# esplash.net
KiCad netlist of a schematic drawn in EAGLE
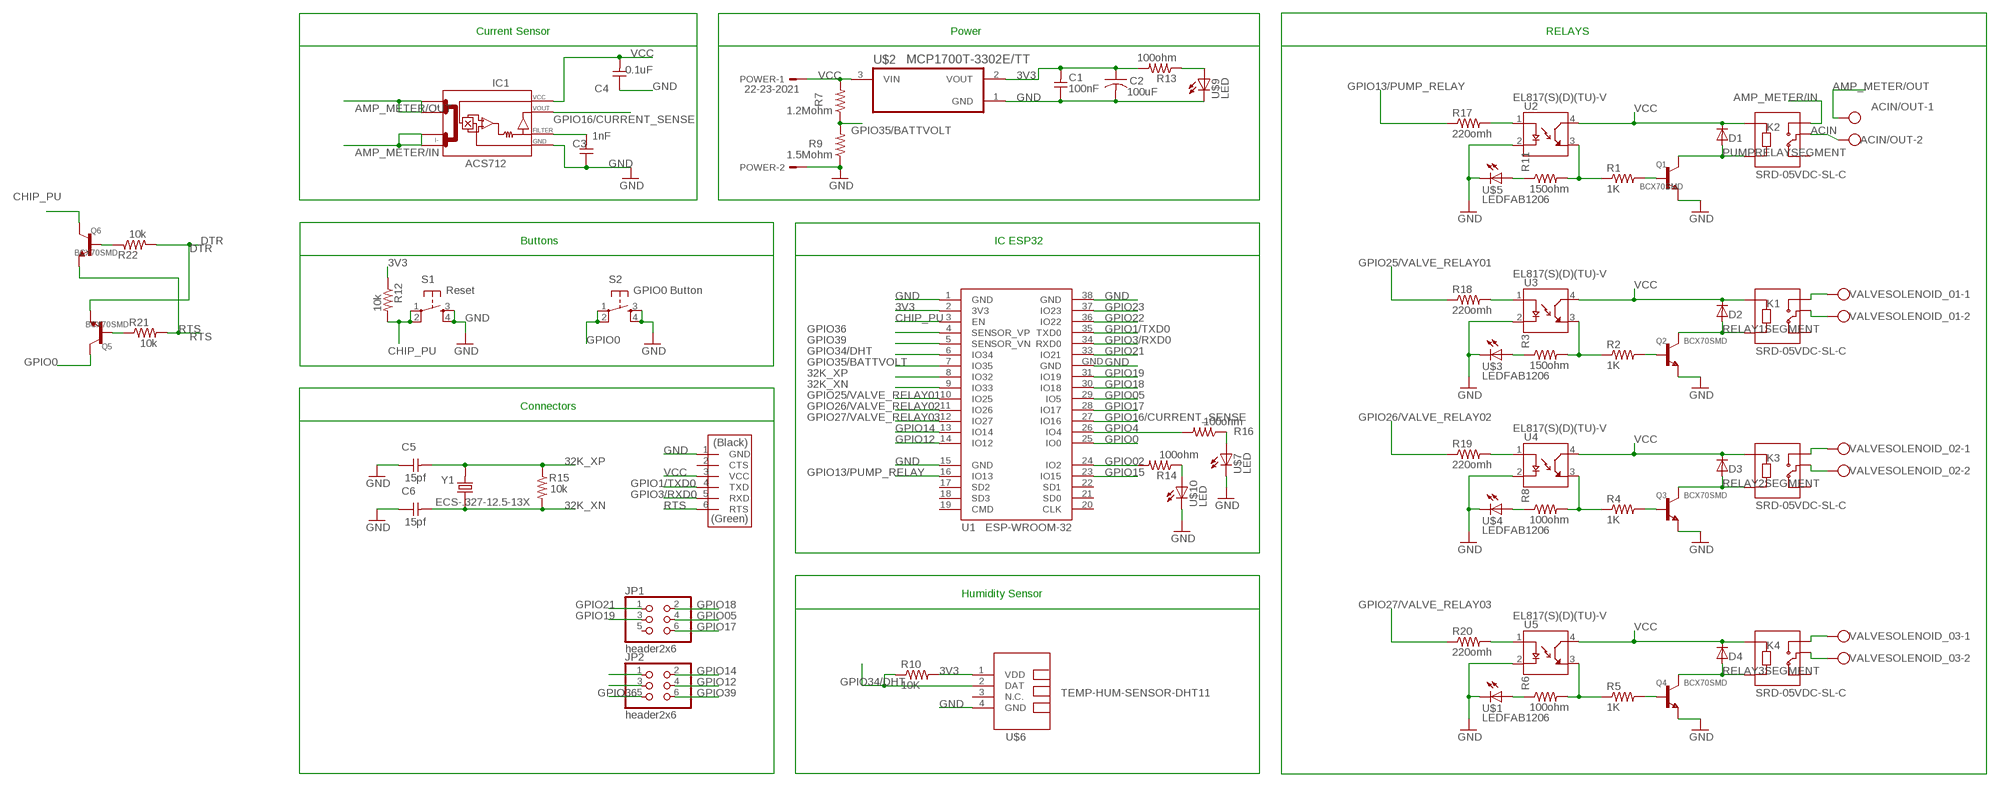
[diagram p0: schematic, sheet 1]

(export (version "E")
  (design (tool "Eeschema 10.0.6"))
  (components
    (comp (ref "ACIN/OUT")
      (value "W237-102")
      (footprint "eagle-import:W237-102")
      (fields (field (name "MPN") "237-102"))
      (libsource (lib "eagle-import") (part "W237-102"))
    )
    (comp (ref "C1")
      (value "100nF")
      (footprint "eagle-import:C1206FAB")
      (libsource (lib "eagle-import") (part "CAP-UNPOLARIZEDFAB"))
    )
    (comp (ref "C2")
      (value "100uF")
      (footprint "eagle-import:C1206FAB")
      (libsource (lib "eagle-import") (part "CAP-US1206FAB"))
    )
    (comp (ref "C3")
      (value "1nF")
      (footprint "eagle-import:C1206FAB")
      (libsource (lib "eagle-import") (part "CAP-UNPOLARIZEDFAB"))
    )
    (comp (ref "C4")
      (value "0.1uF")
      (footprint "eagle-import:C1206FAB")
      (libsource (lib "eagle-import") (part "CAP-UNPOLARIZEDFAB"))
    )
    (comp (ref "C5")
      (value "15pf")
      (footprint "eagle-import:C1206FAB")
      (libsource (lib "eagle-import") (part "CAP-UNPOLARIZEDFAB"))
    )
    (comp (ref "C6")
      (value "15pf")
      (footprint "eagle-import:C1206FAB")
      (libsource (lib "eagle-import") (part "CAP-UNPOLARIZEDFAB"))
    )
    (comp (ref "D1")
      (value "DIODESOD123")
      (footprint "eagle-import:SOD123")
      (libsource (lib "eagle-import") (part "DIODESOD123"))
    )
    (comp (ref "D2")
      (value "DIODESOD123")
      (footprint "eagle-import:SOD123")
      (libsource (lib "eagle-import") (part "DIODESOD123"))
    )
    (comp (ref "D3")
      (value "DIODESOD123")
      (footprint "eagle-import:SOD123")
      (libsource (lib "eagle-import") (part "DIODESOD123"))
    )
    (comp (ref "D4")
      (value "DIODESOD123")
      (footprint "eagle-import:SOD123")
      (libsource (lib "eagle-import") (part "DIODESOD123"))
    )
    (comp (ref "IC1")
      (value "ACS712")
      (footprint "eagle-import:SO08")
      (libsource (lib "eagle-import") (part "ACS712"))
    )
    (comp (ref "JP1")
      (value "header2x6")
      (footprint "eagle-import:2X03")
      (libsource (lib "eagle-import") (part "PINHD-2X3"))
    )
    (comp (ref "JP2")
      (value "header2x6")
      (footprint "eagle-import:2X03")
      (libsource (lib "eagle-import") (part "PINHD-2X3"))
    )
    (comp (ref "K1")
      (value "SRD-05VDC-SL-C")
      (footprint "eagle-import:RELAY_SRD-05VDC-SL-C")
      (fields (field (name "MF") "Songle Relay"))
      (libsource (lib "eagle-import") (part "SRD-05VDC-SL-C"))
    )
    (comp (ref "K2")
      (value "SRD-05VDC-SL-C")
      (footprint "eagle-import:RELAY_SRD-05VDC-SL-C")
      (fields (field (name "MF") "Songle Relay"))
      (libsource (lib "eagle-import") (part "SRD-05VDC-SL-C"))
    )
    (comp (ref "K3")
      (value "SRD-05VDC-SL-C")
      (footprint "eagle-import:RELAY_SRD-05VDC-SL-C")
      (fields (field (name "MF") "Songle Relay"))
      (libsource (lib "eagle-import") (part "SRD-05VDC-SL-C"))
    )
    (comp (ref "K4")
      (value "SRD-05VDC-SL-C")
      (footprint "eagle-import:RELAY_SRD-05VDC-SL-C")
      (fields (field (name "MF") "Songle Relay"))
      (libsource (lib "eagle-import") (part "SRD-05VDC-SL-C"))
    )
    (comp (ref "POWER")
      (value "22-23-2021")
      (footprint "eagle-import:22-23-2021")
      (fields (field (name "MF") "MOLEX"))
      (libsource (lib "eagle-import") (part "22-23-2021"))
    )
    (comp (ref "Q1")
      (value "BCX70SMD")
      (footprint "eagle-import:SOT23")
      (libsource (lib "eagle-import") (part "BCX70SMD"))
    )
    (comp (ref "Q2")
      (value "BCX70SMD")
      (footprint "eagle-import:SOT23")
      (libsource (lib "eagle-import") (part "BCX70SMD"))
    )
    (comp (ref "Q3")
      (value "BCX70SMD")
      (footprint "eagle-import:SOT23")
      (libsource (lib "eagle-import") (part "BCX70SMD"))
    )
    (comp (ref "Q4")
      (value "BCX70SMD")
      (footprint "eagle-import:SOT23")
      (libsource (lib "eagle-import") (part "BCX70SMD"))
    )
    (comp (ref "Q5")
      (value "BCX70SMD")
      (footprint "eagle-import:SOT23")
      (libsource (lib "eagle-import") (part "BCX70SMD"))
    )
    (comp (ref "Q6")
      (value "BCX70SMD")
      (footprint "eagle-import:SOT23")
      (libsource (lib "eagle-import") (part "BCX70SMD"))
    )
    (comp (ref "R1")
      (value "1K")
      (footprint "eagle-import:R1206FAB")
      (libsource (lib "eagle-import") (part "RES-US1206FAB"))
    )
    (comp (ref "R2")
      (value "1K")
      (footprint "eagle-import:R1206FAB")
      (libsource (lib "eagle-import") (part "RES-US1206FAB"))
    )
    (comp (ref "R3")
      (value "150ohm")
      (footprint "eagle-import:R1206FAB")
      (libsource (lib "eagle-import") (part "RES-US1206FAB"))
    )
    (comp (ref "R4")
      (value "1K")
      (footprint "eagle-import:R1206FAB")
      (libsource (lib "eagle-import") (part "RES-US1206FAB"))
    )
    (comp (ref "R5")
      (value "1K")
      (footprint "eagle-import:R1206FAB")
      (libsource (lib "eagle-import") (part "RES-US1206FAB"))
    )
    (comp (ref "R6")
      (value "100ohm")
      (footprint "eagle-import:R1206FAB")
      (libsource (lib "eagle-import") (part "RES-US1206FAB"))
    )
    (comp (ref "R7")
      (value "1.2Mohm")
      (footprint "eagle-import:R1206FAB")
      (libsource (lib "eagle-import") (part "RES-US1206FAB"))
    )
    (comp (ref "R8")
      (value "100ohm")
      (footprint "eagle-import:R1206FAB")
      (libsource (lib "eagle-import") (part "RES-US1206FAB"))
    )
    (comp (ref "R9")
      (value "1.5Mohm")
      (footprint "eagle-import:R1206FAB")
      (libsource (lib "eagle-import") (part "RES-US1206FAB"))
    )
    (comp (ref "R10")
      (value "10K")
      (footprint "eagle-import:R1206FAB")
      (libsource (lib "eagle-import") (part "RES-US1206FAB"))
    )
    (comp (ref "R11")
      (value "150ohm")
      (footprint "eagle-import:R1206FAB")
      (libsource (lib "eagle-import") (part "RES-US1206FAB"))
    )
    (comp (ref "R12")
      (value "10k")
      (footprint "eagle-import:R1206")
      (libsource (lib "eagle-import") (part "RES-US1206"))
    )
    (comp (ref "R13")
      (value "100ohm")
      (footprint "eagle-import:R1206")
      (libsource (lib "eagle-import") (part "RES-US1206"))
    )
    (comp (ref "R14")
      (value "100ohm")
      (footprint "eagle-import:R1206")
      (libsource (lib "eagle-import") (part "RES-US1206"))
    )
    (comp (ref "R15")
      (value "10k")
      (footprint "eagle-import:R1206")
      (libsource (lib "eagle-import") (part "RES-US1206"))
    )
    (comp (ref "R16")
      (value "100ohm")
      (footprint "eagle-import:R1206")
      (libsource (lib "eagle-import") (part "RES-US1206"))
    )
    (comp (ref "R17")
      (value "220omh")
      (footprint "eagle-import:R1206FAB")
      (libsource (lib "eagle-import") (part "RES-US1206FAB"))
    )
    (comp (ref "R18")
      (value "220omh")
      (footprint "eagle-import:R1206FAB")
      (libsource (lib "eagle-import") (part "RES-US1206FAB"))
    )
    (comp (ref "R19")
      (value "220omh")
      (footprint "eagle-import:R1206FAB")
      (libsource (lib "eagle-import") (part "RES-US1206FAB"))
    )
    (comp (ref "R20")
      (value "220omh")
      (footprint "eagle-import:R1206FAB")
      (libsource (lib "eagle-import") (part "RES-US1206FAB"))
    )
    (comp (ref "R21")
      (value "10k")
      (footprint "eagle-import:R1206")
      (libsource (lib "eagle-import") (part "RES-US1206"))
    )
    (comp (ref "R22")
      (value "10k")
      (footprint "eagle-import:R1206")
      (libsource (lib "eagle-import") (part "RES-US1206"))
    )
    (comp (ref "RTS")
      (value "FTDI-SMD-HEADER")
      (footprint "eagle-import:1X06SMD")
      (libsource (lib "eagle-import") (part "FTDI-SMD-HEADER"))
    )
    (comp (ref "S1")
      (value "Reset")
      (footprint "eagle-import:6MM_SWITCH")
      (libsource (lib "eagle-import") (part "6MM_SWITCH6MM_SWITCH"))
    )
    (comp (ref "S2")
      (value "GPIO0 Button")
      (footprint "eagle-import:6MM_SWITCH")
      (libsource (lib "eagle-import") (part "6MM_SWITCH6MM_SWITCH"))
    )
    (comp (ref "U$1")
      (value "LEDFAB1206")
      (footprint "eagle-import:LED1206FAB")
      (libsource (lib "eagle-import") (part "LEDFAB1206"))
    )
    (comp (ref "U$2")
      (value "MCP1700T-3302E/TT")
      (footprint "eagle-import:SOT95P237X112-3N")
      (fields (field (name "MF") "Microchip Technology"))
      (libsource (lib "eagle-import") (part "MCP1700T-3302E/TT"))
    )
    (comp (ref "U$3")
      (value "LEDFAB1206")
      (footprint "eagle-import:LED1206FAB")
      (libsource (lib "eagle-import") (part "LEDFAB1206"))
    )
    (comp (ref "U$4")
      (value "LEDFAB1206")
      (footprint "eagle-import:LED1206FAB")
      (libsource (lib "eagle-import") (part "LEDFAB1206"))
    )
    (comp (ref "U$5")
      (value "LEDFAB1206")
      (footprint "eagle-import:LED1206FAB")
      (libsource (lib "eagle-import") (part "LEDFAB1206"))
    )
    (comp (ref "U$6")
      (value "TEMP-HUM-SENSOR-DHT11")
      (footprint "eagle-import:TEMP-HUM-SENSOR-DHT11")
      (libsource (lib "eagle-import") (part "TEMP-HUM-SENSOR-DHT11"))
    )
    (comp (ref "U$7")
      (value "LED")
      (footprint "eagle-import:LED1206")
      (libsource (lib "eagle-import") (part "LED"))
    )
    (comp (ref "U$9")
      (value "LED")
      (footprint "eagle-import:LED1206")
      (libsource (lib "eagle-import") (part "LED"))
    )
    (comp (ref "U$10")
      (value "LED")
      (footprint "eagle-import:LED1206")
      (libsource (lib "eagle-import") (part "LED"))
    )
    (comp (ref "U1")
      (value "ESP-WROOM-32")
      (footprint "eagle-import:ESP-WROOM-32")
      (libsource (lib "eagle-import") (part "ESP-WROOM-32"))
    )
    (comp (ref "U2")
      (value "EL817(S)(D)(TU)-V")
      (footprint "eagle-import:SOIC254P1030X460-4N")
      (fields (field (name "MF") "Everlight Electronics"))
      (libsource (lib "eagle-import") (part "EL817(S)(D)(TU)-V"))
    )
    (comp (ref "U3")
      (value "EL817(S)(D)(TU)-V")
      (footprint "eagle-import:SOIC254P1030X460-4N")
      (fields (field (name "MF") "Everlight Electronics"))
      (libsource (lib "eagle-import") (part "EL817(S)(D)(TU)-V"))
    )
    (comp (ref "U4")
      (value "EL817(S)(D)(TU)-V")
      (footprint "eagle-import:SOIC254P1030X460-4N")
      (fields (field (name "MF") "Everlight Electronics"))
      (libsource (lib "eagle-import") (part "EL817(S)(D)(TU)-V"))
    )
    (comp (ref "U5")
      (value "EL817(S)(D)(TU)-V")
      (footprint "eagle-import:SOIC254P1030X460-4N")
      (fields (field (name "MF") "Everlight Electronics"))
      (libsource (lib "eagle-import") (part "EL817(S)(D)(TU)-V"))
    )
    (comp (ref "VALVESOLENOID_01")
      (value "W237-102")
      (footprint "eagle-import:W237-102")
      (fields (field (name "MPN") "237-102"))
      (libsource (lib "eagle-import") (part "W237-102"))
    )
    (comp (ref "VALVESOLENOID_02")
      (value "W237-102")
      (footprint "eagle-import:W237-102")
      (fields (field (name "MPN") "237-102"))
      (libsource (lib "eagle-import") (part "W237-102"))
    )
    (comp (ref "VALVESOLENOID_03")
      (value "W237-102")
      (footprint "eagle-import:W237-102")
      (fields (field (name "MPN") "237-102"))
      (libsource (lib "eagle-import") (part "W237-102"))
    )
    (comp (ref "Y1")
      (value "ECS-.327-12.5-13X")
      (footprint "eagle-import:XTAL_ECS-.327-12.5-13X")
      (fields (field (name "MF") "ECS Inc."))
      (libsource (lib "eagle-import") (part "ECS-.327-12.5-13X"))
    )
  )
  (nets
    (net (code "1") (name "/3V3") (class "Default")
      (node (ref "C1") (pin "2") (pinfunction "2_2") (pintype "passive"))
      (node (ref "C2") (pin "1") (pinfunction "1_1") (pintype "passive"))
      (node (ref "R10") (pin "2") (pinfunction "2_2") (pintype "passive"))
      (node (ref "R12") (pin "1") (pinfunction "1_1") (pintype "passive"))
      (node (ref "R13") (pin "2") (pinfunction "2_2") (pintype "passive"))
      (node (ref "U$2") (pin "2") (pinfunction "VOUT_2") (pintype "output"))
      (node (ref "U$6") (pin "1") (pinfunction "VDD_1") (pintype "power_in"))
      (node (ref "U1") (pin "2") (pinfunction "3V3_2") (pintype "power_in"))
    )
    (net (code "2") (name "/32K_XN") (class "Default")
      (node (ref "C6") (pin "2") (pinfunction "2_2") (pintype "passive"))
      (node (ref "R15") (pin "2") (pinfunction "2_2") (pintype "passive"))
      (node (ref "U1") (pin "9") (pinfunction "IO33_9") (pintype "bidirectional"))
      (node (ref "Y1") (pin "1") (pinfunction "1_1") (pintype "passive"))
    )
    (net (code "3") (name "/32K_XP") (class "Default")
      (node (ref "C5") (pin "2") (pinfunction "2_2") (pintype "passive"))
      (node (ref "R15") (pin "1") (pinfunction "1_1") (pintype "passive"))
      (node (ref "U1") (pin "8") (pinfunction "IO32_8") (pintype "bidirectional"))
      (node (ref "Y1") (pin "2") (pinfunction "2_2") (pintype "passive"))
    )
    (net (code "4") (name "/ACIN") (class "Default")
      (node (ref "ACIN/OUT") (pin "2") (pinfunction "KL_2") (pintype "passive"))
      (node (ref "K2") (pin "COM") (pinfunction "COM_COM") (pintype "passive"))
    )
    (net (code "5") (name "/AMP_METER{slash}IN") (class "Default")
      (node (ref "IC1") (pin "3") (pinfunction "I-_0_3") (pintype "bidirectional"))
      (node (ref "IC1") (pin "4") (pinfunction "I-_1_4") (pintype "bidirectional"))
      (node (ref "K2") (pin "NO") (pinfunction "NO_NO") (pintype "passive"))
    )
    (net (code "6") (name "/AMP_METER{slash}OUT") (class "Default")
      (node (ref "ACIN/OUT") (pin "1") (pinfunction "KL_1") (pintype "passive"))
      (node (ref "IC1") (pin "1") (pinfunction "I+_0_1") (pintype "bidirectional"))
      (node (ref "IC1") (pin "2") (pinfunction "I+_1_2") (pintype "bidirectional"))
    )
    (net (code "7") (name "/CHIP_PU") (class "Default")
      (node (ref "Q6") (pin "3") (pinfunction "C_3") (pintype "passive"))
      (node (ref "R12") (pin "2") (pinfunction "2_2") (pintype "passive"))
      (node (ref "S1") (pin "1") (pinfunction "P_1") (pintype "passive"))
      (node (ref "S1") (pin "2") (pinfunction "P1_2") (pintype "passive"))
      (node (ref "U1") (pin "3") (pinfunction "EN_3") (pintype "input"))
    )
    (net (code "8") (name "/DTR") (class "Default")
      (node (ref "Q5") (pin "2") (pinfunction "E_2") (pintype "passive"))
      (node (ref "R22") (pin "2") (pinfunction "2_2") (pintype "passive"))
    )
    (net (code "9") (name "/GPIO0") (class "Default")
      (node (ref "Q5") (pin "3") (pinfunction "C_3") (pintype "passive"))
      (node (ref "S2") (pin "1") (pinfunction "P_1") (pintype "passive"))
      (node (ref "S2") (pin "2") (pinfunction "P1_2") (pintype "passive"))
      (node (ref "U1") (pin "25") (pinfunction "IO0_25") (pintype "bidirectional"))
    )
    (net (code "10") (name "/GPIO1{slash}TXD0") (class "Default")
      (node (ref "RTS") (pin "4") (pinfunction "TXD_4") (pintype "bidirectional"))
      (node (ref "U1") (pin "35") (pinfunction "TXD0_35") (pintype "bidirectional"))
    )
    (net (code "11") (name "/GPIO02") (class "Default")
      (node (ref "R14") (pin "2") (pinfunction "2_2") (pintype "passive"))
      (node (ref "U1") (pin "24") (pinfunction "IO2_24") (pintype "bidirectional"))
    )
    (net (code "12") (name "/GPIO3{slash}RXD0") (class "Default")
      (node (ref "RTS") (pin "5") (pinfunction "RXD_5") (pintype "bidirectional"))
      (node (ref "U1") (pin "34") (pinfunction "RXD0_34") (pintype "bidirectional"))
    )
    (net (code "13") (name "/GPIO4") (class "Default")
      (node (ref "R16") (pin "2") (pinfunction "2_2") (pintype "passive"))
      (node (ref "U1") (pin "26") (pinfunction "IO4_26") (pintype "bidirectional"))
    )
    (net (code "14") (name "/GPIO05") (class "Default")
      (node (ref "JP1") (pin "4") (pinfunction "4_4") (pintype "passive"))
      (node (ref "U1") (pin "29") (pinfunction "IO5_29") (pintype "bidirectional"))
    )
    (net (code "15") (name "/GPIO12") (class "Default")
      (node (ref "JP2") (pin "4") (pinfunction "4_4") (pintype "passive"))
      (node (ref "U1") (pin "14") (pinfunction "IO12_14") (pintype "bidirectional"))
    )
    (net (code "16") (name "/GPIO13{slash}PUMP_RELAY") (class "Default")
      (node (ref "R17") (pin "1") (pinfunction "1_1") (pintype "passive"))
      (node (ref "U1") (pin "16") (pinfunction "IO13_16") (pintype "bidirectional"))
    )
    (net (code "17") (name "/GPIO14") (class "Default")
      (node (ref "JP2") (pin "2") (pinfunction "2_2") (pintype "passive"))
      (node (ref "U1") (pin "13") (pinfunction "IO14_13") (pintype "bidirectional"))
    )
    (net (code "18") (name "/GPIO15") (class "Default")
      (node (ref "U1") (pin "23") (pinfunction "IO15_23") (pintype "bidirectional"))
    )
    (net (code "19") (name "/GPIO16{slash}CURRENT_SENSE") (class "Default")
      (node (ref "IC1") (pin "7") (pinfunction "VOUT_7") (pintype "output"))
      (node (ref "U1") (pin "27") (pinfunction "IO16_27") (pintype "bidirectional"))
    )
    (net (code "20") (name "/GPIO17") (class "Default")
      (node (ref "JP1") (pin "6") (pinfunction "6_6") (pintype "passive"))
      (node (ref "U1") (pin "28") (pinfunction "IO17_28") (pintype "bidirectional"))
    )
    (net (code "21") (name "/GPIO18") (class "Default")
      (node (ref "JP1") (pin "2") (pinfunction "2_2") (pintype "passive"))
      (node (ref "U1") (pin "30") (pinfunction "IO18_30") (pintype "bidirectional"))
    )
    (net (code "22") (name "/GPIO19") (class "Default")
      (node (ref "JP1") (pin "3") (pinfunction "3_3") (pintype "passive"))
      (node (ref "U1") (pin "31") (pinfunction "IO19_31") (pintype "bidirectional"))
    )
    (net (code "23") (name "/GPIO21") (class "Default")
      (node (ref "JP1") (pin "1") (pinfunction "1_1") (pintype "passive"))
      (node (ref "U1") (pin "33") (pinfunction "IO21_33") (pintype "bidirectional"))
    )
    (net (code "24") (name "/GPIO22") (class "Default")
      (node (ref "U1") (pin "36") (pinfunction "IO22_36") (pintype "bidirectional"))
    )
    (net (code "25") (name "/GPIO23") (class "Default")
      (node (ref "U1") (pin "37") (pinfunction "IO23_37") (pintype "bidirectional"))
    )
    (net (code "26") (name "/GPIO25{slash}VALVE_RELAY01") (class "Default")
      (node (ref "R18") (pin "1") (pinfunction "1_1") (pintype "passive"))
      (node (ref "U1") (pin "10") (pinfunction "IO25_10") (pintype "bidirectional"))
    )
    (net (code "27") (name "/GPIO26{slash}VALVE_RELAY02") (class "Default")
      (node (ref "R19") (pin "1") (pinfunction "1_1") (pintype "passive"))
      (node (ref "U1") (pin "11") (pinfunction "IO26_11") (pintype "bidirectional"))
    )
    (net (code "28") (name "/GPIO27{slash}VALVE_RELAY03") (class "Default")
      (node (ref "R20") (pin "1") (pinfunction "1_1") (pintype "passive"))
      (node (ref "U1") (pin "12") (pinfunction "IO27_12") (pintype "bidirectional"))
    )
    (net (code "29") (name "/GPIO34{slash}DHT") (class "Default")
      (node (ref "R10") (pin "1") (pinfunction "1_1") (pintype "passive"))
      (node (ref "U$6") (pin "2") (pinfunction "DAT_2") (pintype "bidirectional"))
      (node (ref "U1") (pin "6") (pinfunction "IO34_6") (pintype "bidirectional"))
    )
    (net (code "30") (name "/GPIO35{slash}BATTVOLT") (class "Default")
      (node (ref "R7") (pin "1") (pinfunction "1_1") (pintype "passive"))
      (node (ref "R9") (pin "2") (pinfunction "2_2") (pintype "passive"))
      (node (ref "U1") (pin "7") (pinfunction "IO35_7") (pintype "bidirectional"))
    )
    (net (code "31") (name "/GPIO36") (class "Default")
      (node (ref "JP2") (pin "5") (pinfunction "5_5") (pintype "passive"))
      (node (ref "U1") (pin "4") (pinfunction "SENSOR_VP_4") (pintype "bidirectional"))
    )
    (net (code "32") (name "/GPIO39") (class "Default")
      (node (ref "JP2") (pin "6") (pinfunction "6_6") (pintype "passive"))
      (node (ref "U1") (pin "5") (pinfunction "SENSOR_VN_5") (pintype "bidirectional"))
    )
    (net (code "33") (name "/PUMPRELAYSEGMENT") (class "Default")
      (node (ref "D1") (pin "ANODE") (pinfunction "A_ANODE") (pintype "passive"))
      (node (ref "K2") (pin "A2") (pinfunction "A2_A2") (pintype "passive"))
      (node (ref "Q1") (pin "3") (pinfunction "C_3") (pintype "passive"))
    )
    (net (code "34") (name "/RELAY1SEGMENT") (class "Default")
      (node (ref "D2") (pin "ANODE") (pinfunction "A_ANODE") (pintype "passive"))
      (node (ref "K1") (pin "A2") (pinfunction "A2_A2") (pintype "passive"))
      (node (ref "Q2") (pin "3") (pinfunction "C_3") (pintype "passive"))
    )
    (net (code "35") (name "/RELAY2SEGMENT") (class "Default")
      (node (ref "D3") (pin "ANODE") (pinfunction "A_ANODE") (pintype "passive"))
      (node (ref "K3") (pin "A2") (pinfunction "A2_A2") (pintype "passive"))
      (node (ref "Q3") (pin "3") (pinfunction "C_3") (pintype "passive"))
    )
    (net (code "36") (name "/RELAY3SEGMENT") (class "Default")
      (node (ref "D4") (pin "ANODE") (pinfunction "A_ANODE") (pintype "passive"))
      (node (ref "K4") (pin "A2") (pinfunction "A2_A2") (pintype "passive"))
      (node (ref "Q4") (pin "3") (pinfunction "C_3") (pintype "passive"))
    )
    (net (code "37") (name "/RTS") (class "Default")
      (node (ref "Q6") (pin "2") (pinfunction "E_2") (pintype "passive"))
      (node (ref "R21") (pin "2") (pinfunction "2_2") (pintype "passive"))
      (node (ref "RTS") (pin "6") (pinfunction "RTS_6") (pintype "bidirectional"))
    )
    (net (code "38") (name "/VCC") (class "Default")
      (node (ref "C4") (pin "2") (pinfunction "2_2") (pintype "passive"))
      (node (ref "D1") (pin "CATHODE") (pinfunction "C_CATHODE") (pintype "passive"))
      (node (ref "D2") (pin "CATHODE") (pinfunction "C_CATHODE") (pintype "passive"))
      (node (ref "D3") (pin "CATHODE") (pinfunction "C_CATHODE") (pintype "passive"))
      (node (ref "D4") (pin "CATHODE") (pinfunction "C_CATHODE") (pintype "passive"))
      (node (ref "IC1") (pin "8") (pinfunction "VCC_8") (pintype "power_in"))
      (node (ref "K1") (pin "A1") (pinfunction "A1_A1") (pintype "passive"))
      (node (ref "K2") (pin "A1") (pinfunction "A1_A1") (pintype "passive"))
      (node (ref "K3") (pin "A1") (pinfunction "A1_A1") (pintype "passive"))
      (node (ref "K4") (pin "A1") (pinfunction "A1_A1") (pintype "passive"))
      (node (ref "POWER") (pin "1") (pinfunction "S_1") (pintype "passive"))
      (node (ref "R7") (pin "2") (pinfunction "2_2") (pintype "passive"))
      (node (ref "RTS") (pin "3") (pinfunction "VCC_3") (pintype "bidirectional"))
      (node (ref "U$2") (pin "3") (pinfunction "VIN_3") (pintype "input"))
      (node (ref "U2") (pin "4") (pinfunction "CT_4") (pintype "passive"))
      (node (ref "U3") (pin "4") (pinfunction "CT_4") (pintype "passive"))
      (node (ref "U4") (pin "4") (pinfunction "CT_4") (pintype "passive"))
      (node (ref "U5") (pin "4") (pinfunction "CT_4") (pintype "passive"))
    )
    (net (code "39") (name "GND") (class "Default")
      (node (ref "C1") (pin "1") (pinfunction "1_1") (pintype "passive"))
      (node (ref "C2") (pin "2") (pinfunction "2_2") (pintype "passive"))
      (node (ref "C3") (pin "1") (pinfunction "1_1") (pintype "passive"))
      (node (ref "C4") (pin "1") (pinfunction "1_1") (pintype "passive"))
      (node (ref "C5") (pin "1") (pinfunction "1_1") (pintype "passive"))
      (node (ref "C6") (pin "1") (pinfunction "1_1") (pintype "passive"))
      (node (ref "IC1") (pin "5") (pinfunction "GND_5") (pintype "power_in"))
      (node (ref "POWER") (pin "2") (pinfunction "S_2") (pintype "passive"))
      (node (ref "Q1") (pin "2") (pinfunction "E_2") (pintype "passive"))
      (node (ref "Q2") (pin "2") (pinfunction "E_2") (pintype "passive"))
      (node (ref "Q3") (pin "2") (pinfunction "E_2") (pintype "passive"))
      (node (ref "Q4") (pin "2") (pinfunction "E_2") (pintype "passive"))
      (node (ref "R9") (pin "1") (pinfunction "1_1") (pintype "passive"))
      (node (ref "RTS") (pin "1") (pinfunction "GND_1") (pintype "bidirectional"))
      (node (ref "S1") (pin "3") (pinfunction "S_3") (pintype "passive"))
      (node (ref "S1") (pin "4") (pinfunction "S1_4") (pintype "passive"))
      (node (ref "S2") (pin "3") (pinfunction "S_3") (pintype "passive"))
      (node (ref "S2") (pin "4") (pinfunction "S1_4") (pintype "passive"))
      (node (ref "U$1") (pin "2") (pinfunction "C_2") (pintype "passive"))
      (node (ref "U$10") (pin "2") (pinfunction "C_2") (pintype "passive"))
      (node (ref "U$2") (pin "1") (pinfunction "GND_1") (pintype "power_in"))
      (node (ref "U$3") (pin "2") (pinfunction "C_2") (pintype "passive"))
      (node (ref "U$4") (pin "2") (pinfunction "C_2") (pintype "passive"))
      (node (ref "U$5") (pin "2") (pinfunction "C_2") (pintype "passive"))
      (node (ref "U$6") (pin "4") (pinfunction "GND_4") (pintype "power_in"))
      (node (ref "U$7") (pin "2") (pinfunction "C_2") (pintype "passive"))
      (node (ref "U$9") (pin "2") (pinfunction "C_2") (pintype "passive"))
      (node (ref "U1") (pin "1") (pinfunction "GND_1") (pintype "power_in"))
      (node (ref "U1") (pin "15") (pinfunction "GND_15") (pintype "power_in"))
      (node (ref "U1") (pin "38") (pinfunction "GND_38") (pintype "power_in"))
      (node (ref "U1") (pin "GND") (pinfunction "GND_GND") (pintype "power_in"))
      (node (ref "U2") (pin "2") (pinfunction "C_2") (pintype "passive"))
      (node (ref "U3") (pin "2") (pinfunction "C_2") (pintype "passive"))
      (node (ref "U4") (pin "2") (pinfunction "C_2") (pintype "passive"))
      (node (ref "U5") (pin "2") (pinfunction "C_2") (pintype "passive"))
    )
    (net (code "40") (name "Net-(IC1-FILTER)") (class "Default")
      (node (ref "C3") (pin "2") (pinfunction "2_2") (pintype "passive"))
      (node (ref "IC1") (pin "6") (pinfunction "FILTER_6") (pintype "bidirectional"))
    )
    (net (code "41") (name "Net-(Q1-B)") (class "Default")
      (node (ref "Q1") (pin "1") (pinfunction "B_1") (pintype "passive"))
      (node (ref "R1") (pin "2") (pinfunction "2_2") (pintype "passive"))
    )
    (net (code "42") (name "Net-(Q2-B)") (class "Default")
      (node (ref "Q2") (pin "1") (pinfunction "B_1") (pintype "passive"))
      (node (ref "R2") (pin "2") (pinfunction "2_2") (pintype "passive"))
    )
    (net (code "43") (name "Net-(Q3-B)") (class "Default")
      (node (ref "Q3") (pin "1") (pinfunction "B_1") (pintype "passive"))
      (node (ref "R4") (pin "2") (pinfunction "2_2") (pintype "passive"))
    )
    (net (code "44") (name "Net-(Q4-B)") (class "Default")
      (node (ref "Q4") (pin "1") (pinfunction "B_1") (pintype "passive"))
      (node (ref "R5") (pin "2") (pinfunction "2_2") (pintype "passive"))
    )
    (net (code "45") (name "Net-(Q5-B)") (class "Default")
      (node (ref "Q5") (pin "1") (pinfunction "B_1") (pintype "passive"))
      (node (ref "R21") (pin "1") (pinfunction "1_1") (pintype "passive"))
    )
    (net (code "46") (name "Net-(Q6-B)") (class "Default")
      (node (ref "Q6") (pin "1") (pinfunction "B_1") (pintype "passive"))
      (node (ref "R22") (pin "1") (pinfunction "1_1") (pintype "passive"))
    )
    (net (code "47") (name "Net-(U$1-A)") (class "Default")
      (node (ref "R6") (pin "1") (pinfunction "1_1") (pintype "passive"))
      (node (ref "U$1") (pin "1") (pinfunction "A_1") (pintype "passive"))
    )
    (net (code "48") (name "Net-(U$3-A)") (class "Default")
      (node (ref "R3") (pin "1") (pinfunction "1_1") (pintype "passive"))
      (node (ref "U$3") (pin "1") (pinfunction "A_1") (pintype "passive"))
    )
    (net (code "49") (name "Net-(U$4-A)") (class "Default")
      (node (ref "R8") (pin "1") (pinfunction "1_1") (pintype "passive"))
      (node (ref "U$4") (pin "1") (pinfunction "A_1") (pintype "passive"))
    )
    (net (code "50") (name "Net-(U$5-A)") (class "Default")
      (node (ref "R11") (pin "1") (pinfunction "1_1") (pintype "passive"))
      (node (ref "U$5") (pin "1") (pinfunction "A_1") (pintype "passive"))
    )
    (net (code "51") (name "Net-(U$7-A)") (class "Default")
      (node (ref "R16") (pin "1") (pinfunction "1_1") (pintype "passive"))
      (node (ref "U$7") (pin "1") (pinfunction "A_1") (pintype "passive"))
    )
    (net (code "52") (name "Net-(U$9-A)") (class "Default")
      (node (ref "R13") (pin "1") (pinfunction "1_1") (pintype "passive"))
      (node (ref "U$9") (pin "1") (pinfunction "A_1") (pintype "passive"))
    )
    (net (code "53") (name "Net-(U$10-A)") (class "Default")
      (node (ref "R14") (pin "1") (pinfunction "1_1") (pintype "passive"))
      (node (ref "U$10") (pin "1") (pinfunction "A_1") (pintype "passive"))
    )
    (net (code "54") (name "Net-(U2-A)") (class "Default")
      (node (ref "R17") (pin "2") (pinfunction "2_2") (pintype "passive"))
      (node (ref "U2") (pin "1") (pinfunction "A_1") (pintype "passive"))
    )
    (net (code "55") (name "Net-(U2-ET)") (class "Default")
      (node (ref "R1") (pin "1") (pinfunction "1_1") (pintype "passive"))
      (node (ref "R11") (pin "2") (pinfunction "2_2") (pintype "passive"))
      (node (ref "U2") (pin "3") (pinfunction "ET_3") (pintype "passive"))
    )
    (net (code "56") (name "Net-(U3-A)") (class "Default")
      (node (ref "R18") (pin "2") (pinfunction "2_2") (pintype "passive"))
      (node (ref "U3") (pin "1") (pinfunction "A_1") (pintype "passive"))
    )
    (net (code "57") (name "Net-(U3-ET)") (class "Default")
      (node (ref "R2") (pin "1") (pinfunction "1_1") (pintype "passive"))
      (node (ref "R3") (pin "2") (pinfunction "2_2") (pintype "passive"))
      (node (ref "U3") (pin "3") (pinfunction "ET_3") (pintype "passive"))
    )
    (net (code "58") (name "Net-(U4-A)") (class "Default")
      (node (ref "R19") (pin "2") (pinfunction "2_2") (pintype "passive"))
      (node (ref "U4") (pin "1") (pinfunction "A_1") (pintype "passive"))
    )
    (net (code "59") (name "Net-(U4-ET)") (class "Default")
      (node (ref "R4") (pin "1") (pinfunction "1_1") (pintype "passive"))
      (node (ref "R8") (pin "2") (pinfunction "2_2") (pintype "passive"))
      (node (ref "U4") (pin "3") (pinfunction "ET_3") (pintype "passive"))
    )
    (net (code "60") (name "Net-(U5-A)") (class "Default")
      (node (ref "R20") (pin "2") (pinfunction "2_2") (pintype "passive"))
      (node (ref "U5") (pin "1") (pinfunction "A_1") (pintype "passive"))
    )
    (net (code "61") (name "Net-(U5-ET)") (class "Default")
      (node (ref "R5") (pin "1") (pinfunction "1_1") (pintype "passive"))
      (node (ref "R6") (pin "2") (pinfunction "2_2") (pintype "passive"))
      (node (ref "U5") (pin "3") (pinfunction "ET_3") (pintype "passive"))
    )
    (net (code "62") (name "Net-(VALVESOLENOID_01A-KL)") (class "Default")
      (node (ref "K1") (pin "NO") (pinfunction "NO_NO") (pintype "passive"))
      (node (ref "VALVESOLENOID_01") (pin "1") (pinfunction "KL_1") (pintype "passive"))
    )
    (net (code "63") (name "Net-(VALVESOLENOID_01B-KL)") (class "Default")
      (node (ref "K1") (pin "COM") (pinfunction "COM_COM") (pintype "passive"))
      (node (ref "VALVESOLENOID_01") (pin "2") (pinfunction "KL_2") (pintype "passive"))
    )
    (net (code "64") (name "Net-(VALVESOLENOID_02A-KL)") (class "Default")
      (node (ref "K3") (pin "NO") (pinfunction "NO_NO") (pintype "passive"))
      (node (ref "VALVESOLENOID_02") (pin "1") (pinfunction "KL_1") (pintype "passive"))
    )
    (net (code "65") (name "Net-(VALVESOLENOID_02B-KL)") (class "Default")
      (node (ref "K3") (pin "COM") (pinfunction "COM_COM") (pintype "passive"))
      (node (ref "VALVESOLENOID_02") (pin "2") (pinfunction "KL_2") (pintype "passive"))
    )
    (net (code "66") (name "Net-(VALVESOLENOID_03A-KL)") (class "Default")
      (node (ref "K4") (pin "NO") (pinfunction "NO_NO") (pintype "passive"))
      (node (ref "VALVESOLENOID_03") (pin "1") (pinfunction "KL_1") (pintype "passive"))
    )
    (net (code "67") (name "Net-(VALVESOLENOID_03B-KL)") (class "Default")
      (node (ref "K4") (pin "COM") (pinfunction "COM_COM") (pintype "passive"))
      (node (ref "VALVESOLENOID_03") (pin "2") (pinfunction "KL_2") (pintype "passive"))
    )
    (net (code "68") (name "unconnected-(JP1-Pad5)") (class "Default")
      (node (ref "JP1") (pin "5") (pinfunction "5_5") (pintype "passive"))
    )
    (net (code "69") (name "unconnected-(JP2-Pad1)") (class "Default")
      (node (ref "JP2") (pin "1") (pinfunction "1_1") (pintype "passive"))
    )
    (net (code "70") (name "unconnected-(JP2-Pad3)") (class "Default")
      (node (ref "JP2") (pin "3") (pinfunction "3_3") (pintype "passive"))
    )
    (net (code "71") (name "unconnected-(K1-PadNC)") (class "Default")
      (node (ref "K1") (pin "NC") (pinfunction "NC_NC") (pintype "passive"))
    )
    (net (code "72") (name "unconnected-(K2-PadNC)") (class "Default")
      (node (ref "K2") (pin "NC") (pinfunction "NC_NC") (pintype "passive"))
    )
    (net (code "73") (name "unconnected-(K3-PadNC)") (class "Default")
      (node (ref "K3") (pin "NC") (pinfunction "NC_NC") (pintype "passive"))
    )
    (net (code "74") (name "unconnected-(K4-PadNC)") (class "Default")
      (node (ref "K4") (pin "NC") (pinfunction "NC_NC") (pintype "passive"))
    )
    (net (code "75") (name "unconnected-(RTS-CTS-Pad2)") (class "Default")
      (node (ref "RTS") (pin "2") (pinfunction "CTS_2") (pintype "bidirectional"))
    )
    (net (code "76") (name "unconnected-(U$6-N.C.-Pad3)") (class "Default")
      (node (ref "U$6") (pin "3") (pinfunction "N.C._3") (pintype "passive"))
    )
    (net (code "77") (name "unconnected-(U1-CLK-Pad20)") (class "Default")
      (node (ref "U1") (pin "20") (pinfunction "CLK_20") (pintype "bidirectional"))
    )
    (net (code "78") (name "unconnected-(U1-CMD-Pad19)") (class "Default")
      (node (ref "U1") (pin "19") (pinfunction "CMD_19") (pintype "bidirectional"))
    )
    (net (code "79") (name "unconnected-(U1-SD0-Pad21)") (class "Default")
      (node (ref "U1") (pin "21") (pinfunction "SD0_21") (pintype "bidirectional"))
    )
    (net (code "80") (name "unconnected-(U1-SD1-Pad22)") (class "Default")
      (node (ref "U1") (pin "22") (pinfunction "SD1_22") (pintype "bidirectional"))
    )
    (net (code "81") (name "unconnected-(U1-SD2-Pad17)") (class "Default")
      (node (ref "U1") (pin "17") (pinfunction "SD2_17") (pintype "bidirectional"))
    )
    (net (code "82") (name "unconnected-(U1-SD3-Pad18)") (class "Default")
      (node (ref "U1") (pin "18") (pinfunction "SD3_18") (pintype "bidirectional"))
    )
  )
)
